# NRF24L01.net
KiCad netlist of a schematic drawn in Altium Designer
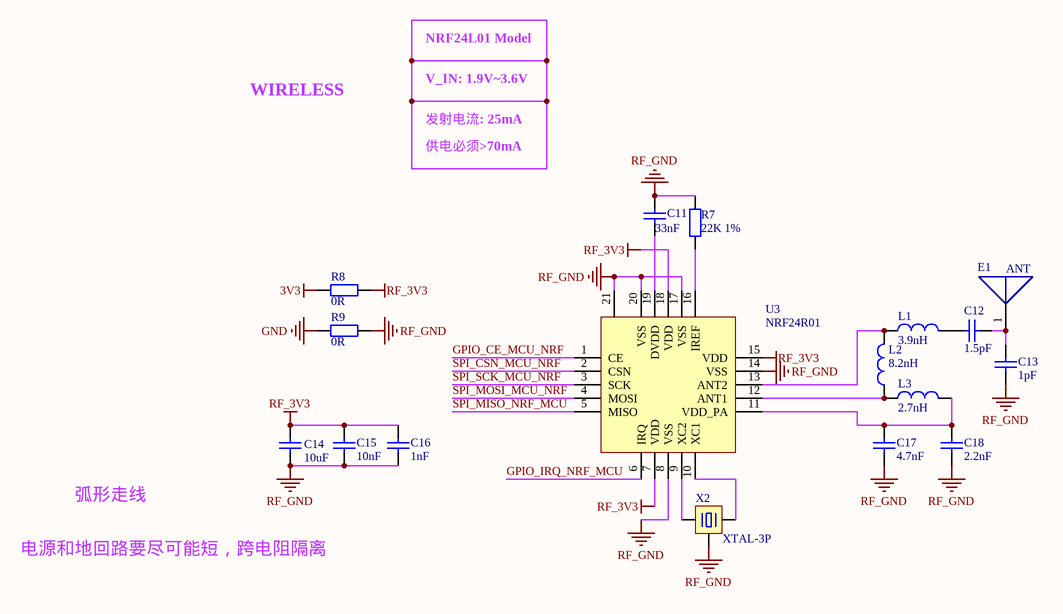
[diagram p0: NRF24L01.SchDoc]

(export (version "E")
  (design (tool "Eeschema 10.0.6"))
  (components
    (comp (ref "C11")
      (value "33nF")
      (footprint "CAP-0402-M")
      (description "贴片陶瓷电容")
      (libsource (lib "Miscellaneous Base") (part "CAP"))
    )
    (comp (ref "C12")
      (value "1.5pF")
      (footprint "Cap-0402-M")
      (description "贴片陶瓷电容")
      (libsource (lib "Miscellaneous Base") (part "CAP"))
    )
    (comp (ref "C13")
      (value "1pF")
      (footprint "Cap-0402-M")
      (description "贴片陶瓷电容")
      (libsource (lib "Miscellaneous Base") (part "CAP"))
    )
    (comp (ref "C14")
      (value "10uF")
      (footprint "Cap-0603-M")
      (description "贴片陶瓷电容")
      (libsource (lib "Miscellaneous Base") (part "CAP"))
    )
    (comp (ref "C15")
      (value "10nF")
      (footprint "CAP-0402-M")
      (description "贴片陶瓷电容")
      (libsource (lib "Miscellaneous Base") (part "CAP"))
    )
    (comp (ref "C16")
      (value "1nF")
      (footprint "CAP-0402-M")
      (description "贴片陶瓷电容")
      (libsource (lib "Miscellaneous Base") (part "CAP"))
    )
    (comp (ref "C17")
      (value "4.7nF")
      (footprint "Cap-0402-M")
      (description "贴片陶瓷电容")
      (libsource (lib "Miscellaneous Base") (part "CAP"))
    )
    (comp (ref "C18")
      (value "2.2nF")
      (footprint "Cap-0402-M")
      (description "贴片陶瓷电容")
      (libsource (lib "Miscellaneous Base") (part "CAP"))
    )
    (comp (ref "E1")
      (value "ANT")
      (footprint "AN2051-245")
      (fields (field (name "PUBLISHER") "mazhongwei"))
      (libsource (lib "Miscellaneous Others") (part "ANT"))
    )
    (comp (ref "L1")
      (value "3.9nH")
      (footprint "L-0402")
      (description "贴片电感")
      (libsource (lib "Miscellaneous Base") (part "INDUCTOR"))
    )
    (comp (ref "L2")
      (value "8.2nH")
      (footprint "L-0402")
      (description "贴片电感")
      (libsource (lib "Miscellaneous Base") (part "INDUCTOR"))
    )
    (comp (ref "L3")
      (value "2.7nH")
      (footprint "L-0402")
      (description "贴片电感")
      (libsource (lib "Miscellaneous Base") (part "INDUCTOR"))
    )
    (comp (ref "R7")
      (value "22K 1%")
      (footprint "Res-0402-M")
      (description "贴片电阻")
      (libsource (lib "") (part "RES_1"))
    )
    (comp (ref "R8")
      (value "0R")
      (footprint "Res-0402-M")
      (description "贴片电阻")
      (libsource (lib "Miscellaneous Base") (part "RES"))
    )
    (comp (ref "R9")
      (value "0R")
      (footprint "Res-0402-M")
      (description "贴片电阻")
      (libsource (lib "Miscellaneous Base") (part "RES"))
    )
    (comp (ref "U3")
      (value "NRF24R01")
      (footprint "QFN20 4x4")
      (description "2.4G无线")
      (libsource (lib "Miscellaneous IC") (part "NRF24R01"))
    )
    (comp (ref "X2")
      (value "XTAL-3P")
      (footprint "OSC 3213-3P")
      (description "3脚无源晶振带电容")
      (libsource (lib "Miscellaneous XTAL") (part "XTAL-3P"))
    )
  )
  (nets
    (net (code "1") (name "/GPIO_CE_MCU_NRF") (class "Default")
      (node (ref "U3") (pin "1") (pinfunction "CE_1") (pintype "passive"))
    )
    (net (code "2") (name "/GPIO_IRQ_NRF_MCU") (class "Default")
      (node (ref "U3") (pin "6") (pinfunction "IRQ_6") (pintype "passive"))
    )
    (net (code "3") (name "/SPI_CSN_MCU_NRF") (class "Default")
      (node (ref "U3") (pin "2") (pinfunction "CSN_2") (pintype "passive"))
    )
    (net (code "4") (name "/SPI_MISO_NRF_MCU") (class "Default")
      (node (ref "U3") (pin "5") (pinfunction "MISO_5") (pintype "passive"))
    )
    (net (code "5") (name "/SPI_MOSI_MCU_NRF") (class "Default")
      (node (ref "U3") (pin "4") (pinfunction "MOSI_4") (pintype "passive"))
    )
    (net (code "6") (name "/SPI_SCK_MCU_NRF") (class "Default")
      (node (ref "U3") (pin "3") (pinfunction "SCK_3") (pintype "passive"))
    )
    (net (code "7") (name "3V3") (class "Default")
      (node (ref "R8") (pin "1") (pinfunction "1_1") (pintype "passive"))
    )
    (net (code "8") (name "GND") (class "Default")
      (node (ref "R9") (pin "1") (pinfunction "1_1") (pintype "passive"))
    )
    (net (code "9") (name "Net-(C12-Pad1)") (class "Default")
      (node (ref "C12") (pin "1") (pinfunction "1_1") (pintype "passive"))
      (node (ref "L1") (pin "2") (pinfunction "2_2") (pintype "passive"))
    )
    (net (code "10") (name "Net-(C12-Pad2)") (class "Default")
      (node (ref "C12") (pin "2") (pinfunction "2_2") (pintype "passive"))
      (node (ref "C13") (pin "2") (pinfunction "2_2") (pintype "passive"))
      (node (ref "E1") (pin "1") (pinfunction "1_1") (pintype "passive"))
    )
    (net (code "11") (name "Net-(U3-ANT1)") (class "Default")
      (node (ref "L2") (pin "1") (pinfunction "1_1") (pintype "passive"))
      (node (ref "L3") (pin "1") (pinfunction "1_1") (pintype "passive"))
      (node (ref "U3") (pin "12") (pinfunction "ANT1_12") (pintype "passive"))
    )
    (net (code "12") (name "Net-(U3-ANT2)") (class "Default")
      (node (ref "L1") (pin "1") (pinfunction "1_1") (pintype "passive"))
      (node (ref "L2") (pin "2") (pinfunction "2_2") (pintype "passive"))
      (node (ref "U3") (pin "13") (pinfunction "ANT2_13") (pintype "passive"))
    )
    (net (code "13") (name "Net-(U3-DVDD)") (class "Default")
      (node (ref "C11") (pin "2") (pinfunction "2_2") (pintype "passive"))
      (node (ref "U3") (pin "19") (pinfunction "DVDD_19") (pintype "passive"))
    )
    (net (code "14") (name "Net-(U3-IREF)") (class "Default")
      (node (ref "R7") (pin "2") (pinfunction "2_2") (pintype "passive"))
      (node (ref "U3") (pin "16") (pinfunction "IREF_16") (pintype "passive"))
    )
    (net (code "15") (name "Net-(U3-VDD_PA)") (class "Default")
      (node (ref "C17") (pin "2") (pinfunction "2_2") (pintype "passive"))
      (node (ref "C18") (pin "2") (pinfunction "2_2") (pintype "passive"))
      (node (ref "L3") (pin "2") (pinfunction "2_2") (pintype "passive"))
      (node (ref "U3") (pin "11") (pinfunction "VDD_PA_11") (pintype "passive"))
    )
    (net (code "16") (name "Net-(U3-XC1)") (class "Default")
      (node (ref "U3") (pin "10") (pinfunction "XC1_10") (pintype "passive"))
      (node (ref "X2") (pin "3") (pinfunction "3_3") (pintype "passive"))
    )
    (net (code "17") (name "Net-(U3-XC2)") (class "Default")
      (node (ref "U3") (pin "9") (pinfunction "XC2_9") (pintype "passive"))
      (node (ref "X2") (pin "1") (pinfunction "1_1") (pintype "passive"))
    )
    (net (code "18") (name "RF_3V3") (class "Default")
      (node (ref "C14") (pin "2") (pinfunction "2_2") (pintype "passive"))
      (node (ref "C15") (pin "2") (pinfunction "2_2") (pintype "passive"))
      (node (ref "C16") (pin "2") (pinfunction "2_2") (pintype "passive"))
      (node (ref "R8") (pin "2") (pinfunction "2_2") (pintype "passive"))
      (node (ref "U3") (pin "15") (pinfunction "VDD_15") (pintype "passive"))
      (node (ref "U3") (pin "18") (pinfunction "VDD_18") (pintype "passive"))
      (node (ref "U3") (pin "7") (pinfunction "VDD_7") (pintype "passive"))
    )
    (net (code "19") (name "RF_GND") (class "Default")
      (node (ref "C11") (pin "1") (pinfunction "1_1") (pintype "passive"))
      (node (ref "C13") (pin "1") (pinfunction "1_1") (pintype "passive"))
      (node (ref "C14") (pin "1") (pinfunction "1_1") (pintype "passive"))
      (node (ref "C15") (pin "1") (pinfunction "1_1") (pintype "passive"))
      (node (ref "C16") (pin "1") (pinfunction "1_1") (pintype "passive"))
      (node (ref "C17") (pin "1") (pinfunction "1_1") (pintype "passive"))
      (node (ref "C18") (pin "1") (pinfunction "1_1") (pintype "passive"))
      (node (ref "R7") (pin "1") (pinfunction "1_1") (pintype "passive"))
      (node (ref "R9") (pin "2") (pinfunction "2_2") (pintype "passive"))
      (node (ref "U3") (pin "14") (pinfunction "VSS_14") (pintype "passive"))
      (node (ref "U3") (pin "17") (pinfunction "VSS_17") (pintype "passive"))
      (node (ref "U3") (pin "20") (pinfunction "VSS_20") (pintype "passive"))
      (node (ref "U3") (pin "21") (pintype "passive"))
      (node (ref "U3") (pin "8") (pinfunction "VSS_8") (pintype "passive"))
      (node (ref "X2") (pin "2") (pinfunction "2_2") (pintype "passive"))
    )
  )
)
